# S7G7_footprint_simplified_w_ethernet_v1p.net
KiCad netlist of a schematic drawn in EAGLE
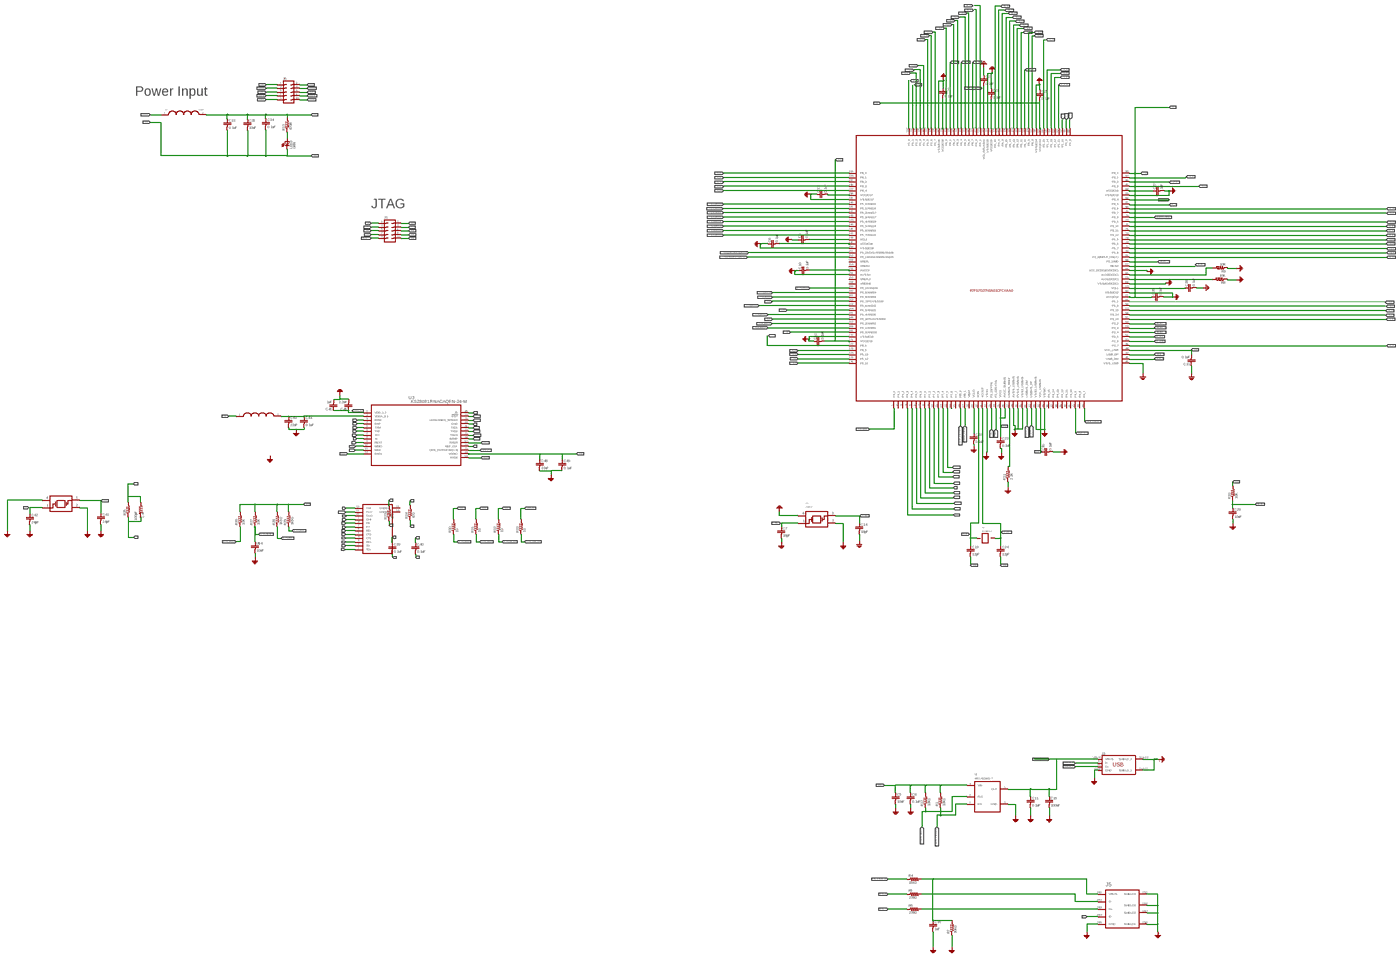
[diagram p0: schematic, sheet 1, overview]
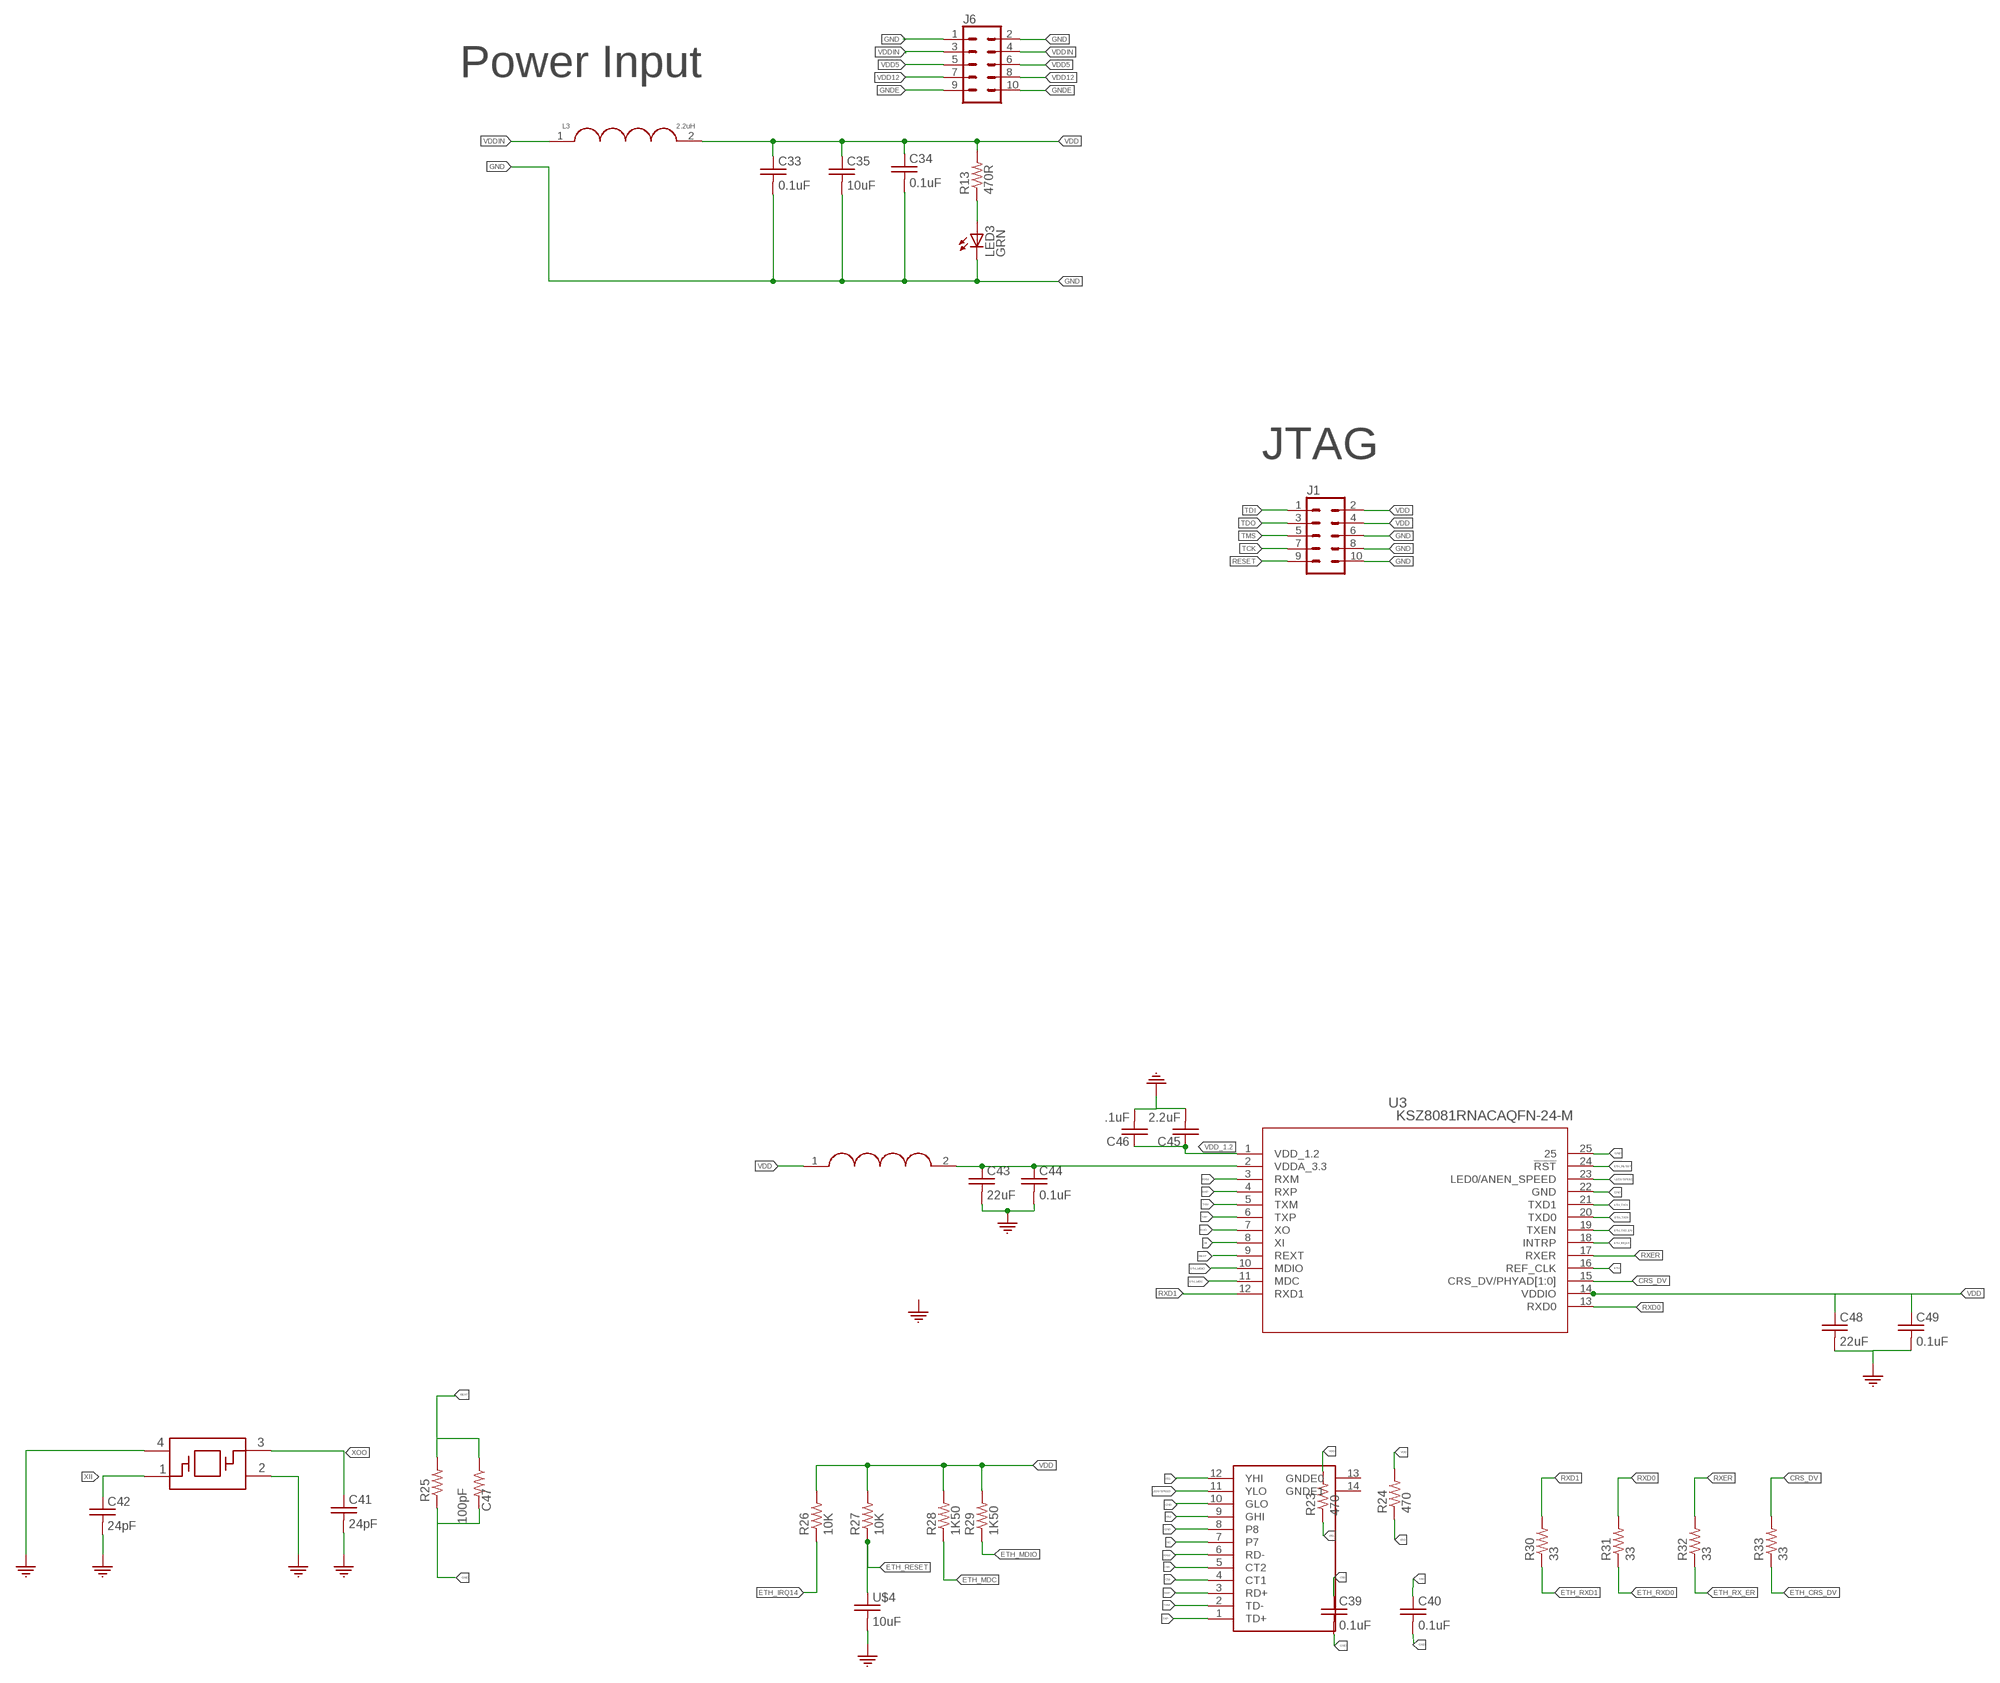
[diagram p1: schematic, sheet 1, part 1 of 4]
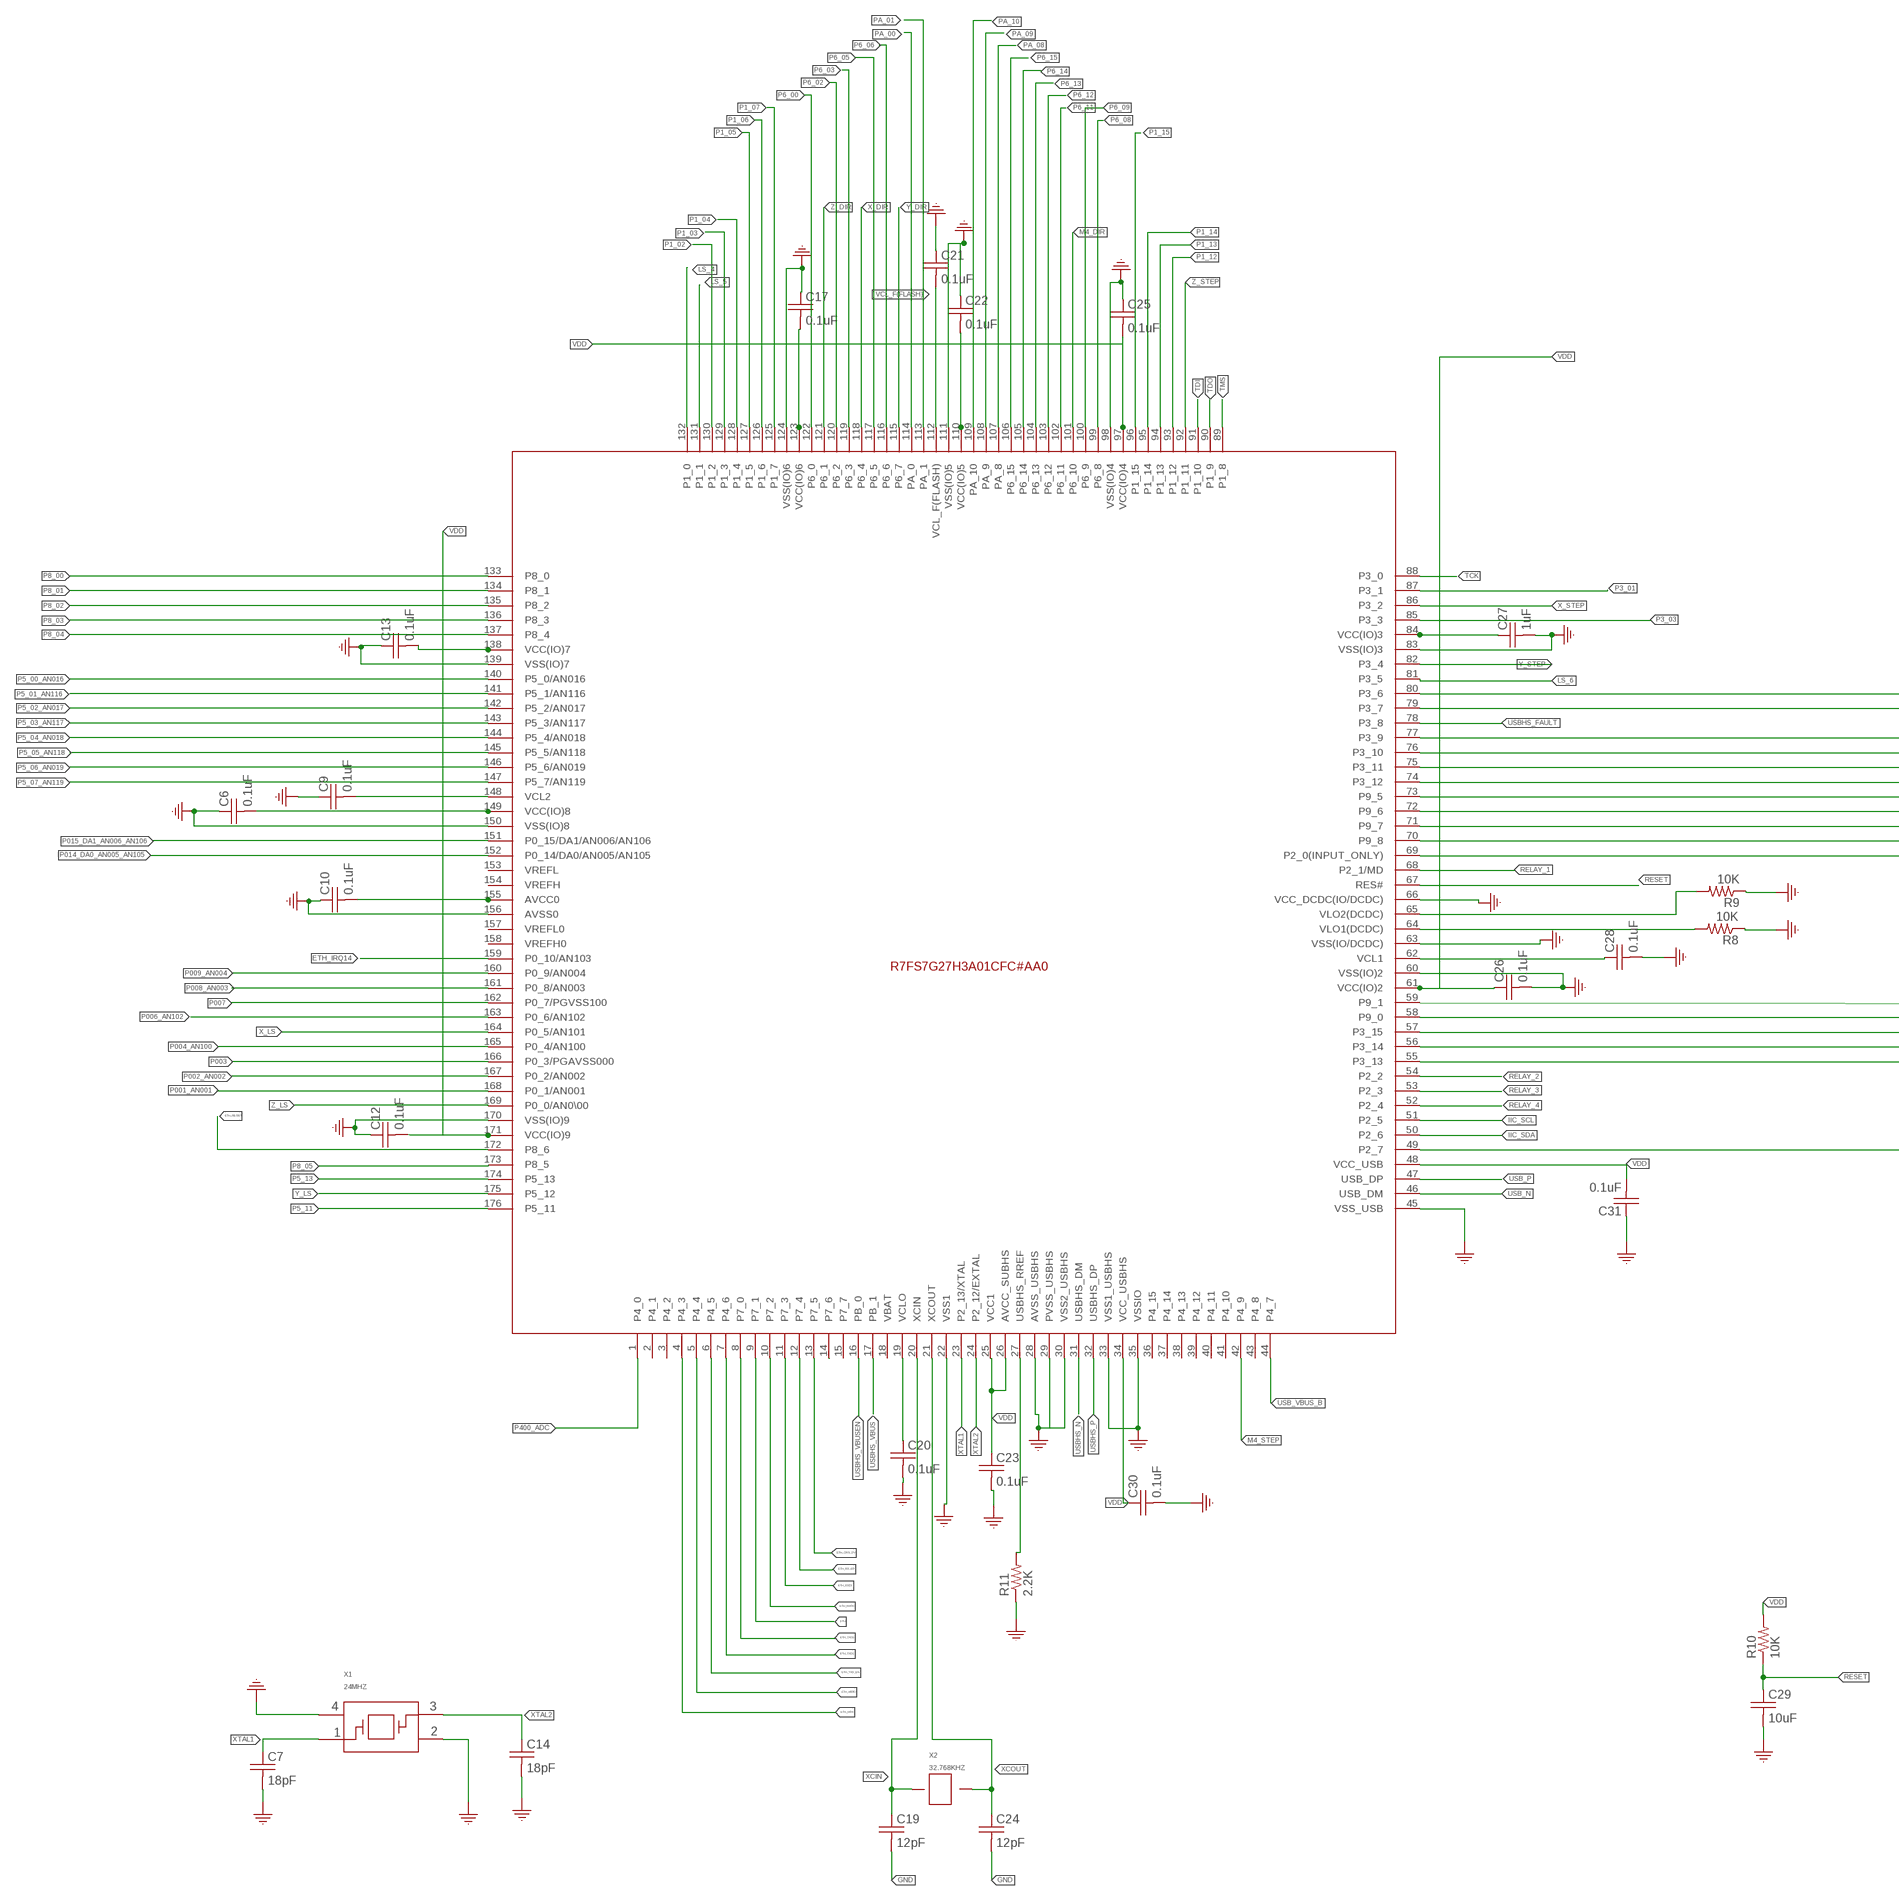
[diagram p2: schematic, sheet 1, part 2 of 4]
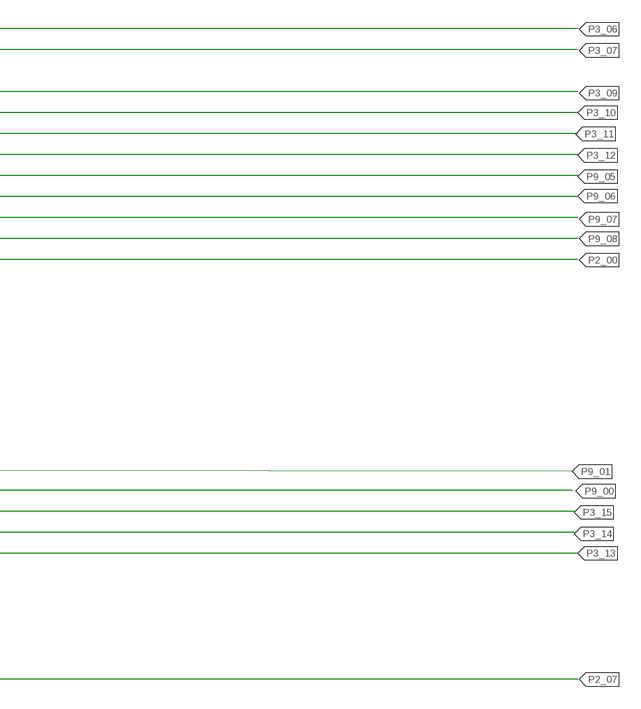
[diagram p3: schematic, sheet 1, part 3 of 4]
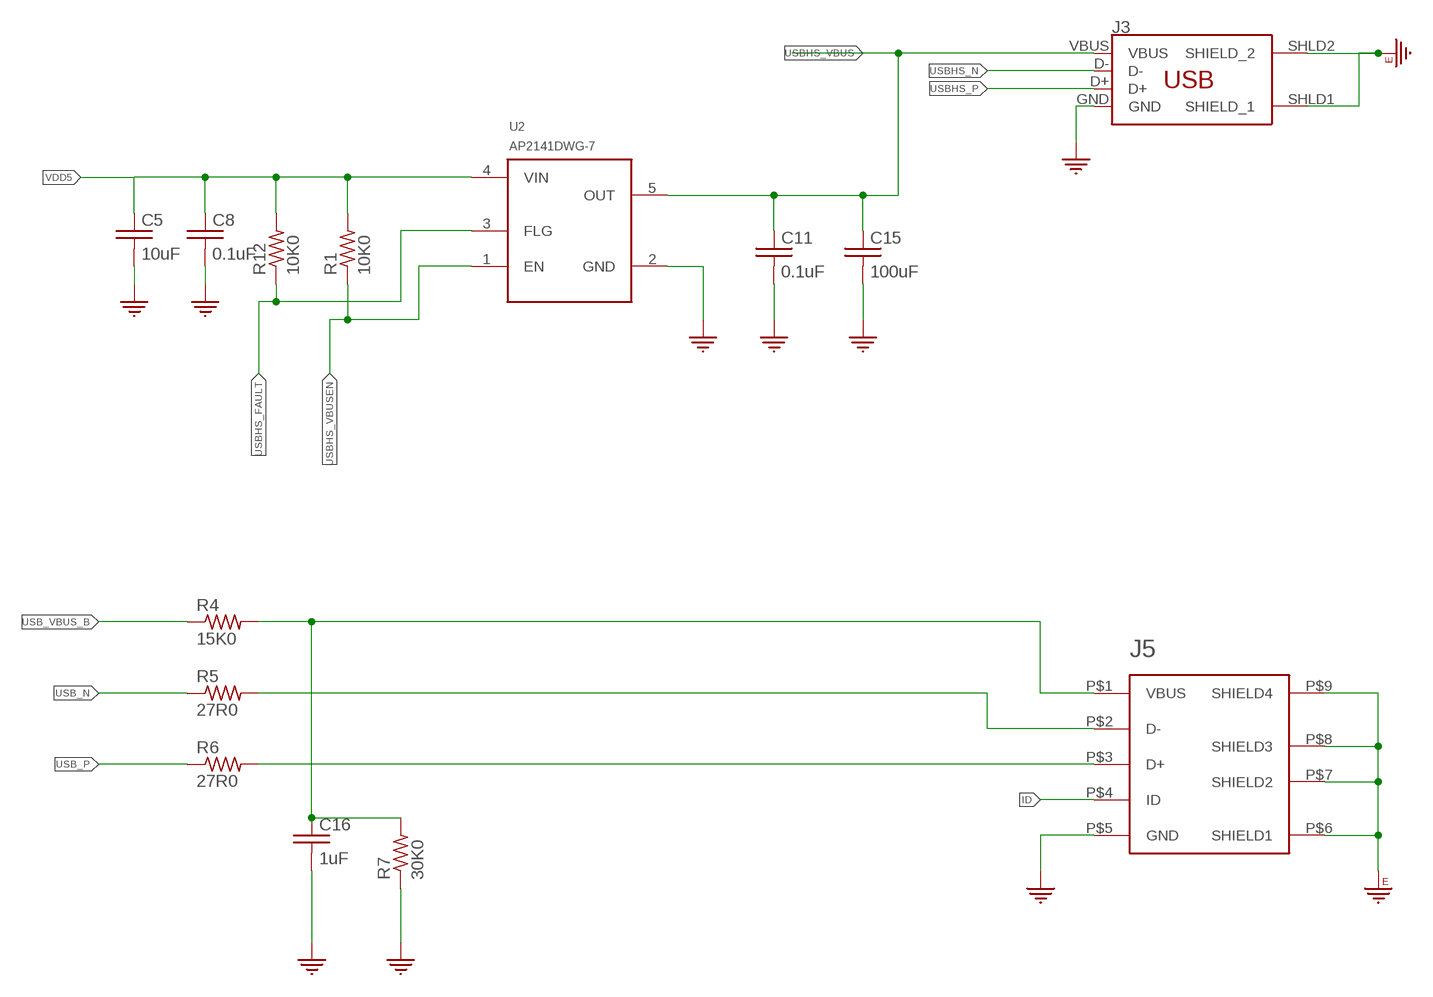
[diagram p4: schematic, sheet 1, part 4 of 4]

(export (version "E")
  (design (tool "Eeschema 10.0.6"))
  (components
    (comp (ref "C5")
      (value "10uF")
      (footprint "eagle-import:0402")
      (libsource (lib "eagle-import") (part "C_0402"))
    )
    (comp (ref "C6")
      (value "0.1uF")
      (footprint "eagle-import:0402")
      (libsource (lib "eagle-import") (part "C_0402"))
    )
    (comp (ref "C7")
      (value "18pF")
      (footprint "eagle-import:0402")
      (libsource (lib "eagle-import") (part "C_0402"))
    )
    (comp (ref "C8")
      (value "0.1uF")
      (footprint "eagle-import:0402")
      (libsource (lib "eagle-import") (part "C_0402"))
    )
    (comp (ref "C9")
      (value "0.1uF")
      (footprint "eagle-import:0402")
      (libsource (lib "eagle-import") (part "C_0402"))
    )
    (comp (ref "C10")
      (value "0.1uF")
      (footprint "eagle-import:0402")
      (libsource (lib "eagle-import") (part "C_0402"))
    )
    (comp (ref "C11")
      (value "0.1uF")
      (footprint "eagle-import:0402")
      (libsource (lib "eagle-import") (part "C_0402"))
    )
    (comp (ref "C12")
      (value "0.1uF")
      (footprint "eagle-import:0402")
      (libsource (lib "eagle-import") (part "C_0402"))
    )
    (comp (ref "C13")
      (value "0.1uF")
      (footprint "eagle-import:0402")
      (libsource (lib "eagle-import") (part "C_0402"))
    )
    (comp (ref "C14")
      (value "18pF")
      (footprint "eagle-import:0402")
      (libsource (lib "eagle-import") (part "C_0402"))
    )
    (comp (ref "C15")
      (value "100uF")
      (footprint "eagle-import:C1210")
      (libsource (lib "eagle-import") (part "C_1210"))
    )
    (comp (ref "C16")
      (value "1uF")
      (footprint "eagle-import:0402")
      (libsource (lib "eagle-import") (part "C_0402"))
    )
    (comp (ref "C17")
      (value "0.1uF")
      (footprint "eagle-import:0402")
      (libsource (lib "eagle-import") (part "C_0402"))
    )
    (comp (ref "C19")
      (value "12pF")
      (footprint "eagle-import:0402")
      (libsource (lib "eagle-import") (part "C_0402"))
    )
    (comp (ref "C20")
      (value "0.1uF")
      (footprint "eagle-import:0402")
      (libsource (lib "eagle-import") (part "C_0402"))
    )
    (comp (ref "C21")
      (value "0.1uF")
      (footprint "eagle-import:0402")
      (libsource (lib "eagle-import") (part "C_0402"))
    )
    (comp (ref "C22")
      (value "0.1uF")
      (footprint "eagle-import:0402")
      (libsource (lib "eagle-import") (part "C_0402"))
    )
    (comp (ref "C23")
      (value "0.1uF")
      (footprint "eagle-import:0402")
      (libsource (lib "eagle-import") (part "C_0402"))
    )
    (comp (ref "C24")
      (value "12pF")
      (footprint "eagle-import:0402")
      (libsource (lib "eagle-import") (part "C_0402"))
    )
    (comp (ref "C25")
      (value "0.1uF")
      (footprint "eagle-import:0402")
      (libsource (lib "eagle-import") (part "C_0402"))
    )
    (comp (ref "C26")
      (value "0.1uF")
      (footprint "eagle-import:0402")
      (libsource (lib "eagle-import") (part "C_0402"))
    )
    (comp (ref "C27")
      (value "1uF")
      (footprint "eagle-import:0402")
      (libsource (lib "eagle-import") (part "C_0402"))
    )
    (comp (ref "C28")
      (value "0.1uF")
      (footprint "eagle-import:0402")
      (libsource (lib "eagle-import") (part "C_0402"))
    )
    (comp (ref "C29")
      (value "10uF")
      (footprint "eagle-import:0402")
      (libsource (lib "eagle-import") (part "C_0402"))
    )
    (comp (ref "C30")
      (value "0.1uF")
      (footprint "eagle-import:0402")
      (libsource (lib "eagle-import") (part "C_0402"))
    )
    (comp (ref "C31")
      (value "0.1uF")
      (footprint "eagle-import:0402")
      (libsource (lib "eagle-import") (part "C_0402"))
    )
    (comp (ref "C33")
      (value "0.1uF")
      (footprint "eagle-import:0402")
      (libsource (lib "eagle-import") (part "C_0402"))
    )
    (comp (ref "C34")
      (value "0.1uF")
      (footprint "eagle-import:0402")
      (libsource (lib "eagle-import") (part "C_0402"))
    )
    (comp (ref "C35")
      (value "10uF")
      (footprint "eagle-import:0402")
      (libsource (lib "eagle-import") (part "C_0402"))
    )
    (comp (ref "C39")
      (value "0.1uF")
      (footprint "eagle-import:0402")
      (libsource (lib "eagle-import") (part "C_0402"))
    )
    (comp (ref "C40")
      (value "0.1uF")
      (footprint "eagle-import:0402")
      (libsource (lib "eagle-import") (part "C_0402"))
    )
    (comp (ref "C41")
      (value "24pF")
      (footprint "eagle-import:0402")
      (libsource (lib "eagle-import") (part "C_0402"))
    )
    (comp (ref "C42")
      (value "24pF")
      (footprint "eagle-import:0402")
      (libsource (lib "eagle-import") (part "C_0402"))
    )
    (comp (ref "C43")
      (value "22uF")
      (footprint "eagle-import:0603")
      (libsource (lib "eagle-import") (part "C_0603"))
    )
    (comp (ref "C44")
      (value "0.1uF")
      (footprint "eagle-import:0402")
      (libsource (lib "eagle-import") (part "C_0402"))
    )
    (comp (ref "C45")
      (value "2.2uF")
      (footprint "eagle-import:0402")
      (libsource (lib "eagle-import") (part "C_0402"))
    )
    (comp (ref "C46")
      (value ".1uF")
      (footprint "eagle-import:0402")
      (libsource (lib "eagle-import") (part "C_0402"))
    )
    (comp (ref "C47")
      (value "100pF")
      (footprint "eagle-import:0402")
      (libsource (lib "eagle-import") (part "R_0402"))
    )
    (comp (ref "C48")
      (value "22uF")
      (footprint "eagle-import:0603")
      (libsource (lib "eagle-import") (part "C_0603"))
    )
    (comp (ref "C49")
      (value "0.1uF")
      (footprint "eagle-import:0402")
      (libsource (lib "eagle-import") (part "C_0402"))
    )
    (comp (ref "FB2/2")
      (value "FB_0805_120_OHM")
      (footprint "eagle-import:0805")
      (libsource (lib "eagle-import") (part "FB_0805_120_OHM"))
    )
    (comp (ref "J1")
      (value "CONN_05X2PTH")
      (footprint "eagle-import:2X5")
      (libsource (lib "eagle-import") (part "CONN_05X2PTH"))
    )
    (comp (ref "J3")
      (value "USB_A")
      (footprint "eagle-import:USB_A_SMT")
      (libsource (lib "eagle-import") (part "USB_A"))
    )
    (comp (ref "J5")
      (value "USB_MICRO-B")
      (footprint "eagle-import:USB_MICRO-B")
      (libsource (lib "eagle-import") (part "USB_MICRO-B"))
    )
    (comp (ref "J6")
      (value "CONN_05X2PTH")
      (footprint "eagle-import:2X5")
      (libsource (lib "eagle-import") (part "CONN_05X2PTH"))
    )
    (comp (ref "L3")
      (value "2.2uH")
      (footprint "eagle-import:1008_(2520_METRIC)")
      (libsource (lib "eagle-import") (part "INDUCTOR_1008_2.2_MH_1.3A"))
    )
    (comp (ref "LED3")
      (value "LED_0805_GREEN")
      (footprint "eagle-import:LED_0805_GREEN")
      (libsource (lib "eagle-import") (part "LED_0805_GREEN"))
    )
    (comp (ref "R1")
      (value "10K0")
      (footprint "eagle-import:0402")
      (libsource (lib "eagle-import") (part "R_0402"))
    )
    (comp (ref "R4")
      (value "15K0")
      (footprint "eagle-import:0402")
      (libsource (lib "eagle-import") (part "R_0402"))
    )
    (comp (ref "R5")
      (value "27R0")
      (footprint "eagle-import:0402")
      (libsource (lib "eagle-import") (part "R_0402"))
    )
    (comp (ref "R6")
      (value "27R0")
      (footprint "eagle-import:0402")
      (libsource (lib "eagle-import") (part "R_0402"))
    )
    (comp (ref "R7")
      (value "30K0")
      (footprint "eagle-import:0402")
      (libsource (lib "eagle-import") (part "R_0402"))
    )
    (comp (ref "R8")
      (value "10K")
      (footprint "eagle-import:0402")
      (libsource (lib "eagle-import") (part "R_0402"))
    )
    (comp (ref "R9")
      (value "10K")
      (footprint "eagle-import:0402")
      (libsource (lib "eagle-import") (part "R_0402"))
    )
    (comp (ref "R10")
      (value "10K")
      (footprint "eagle-import:0402")
      (libsource (lib "eagle-import") (part "R_0402"))
    )
    (comp (ref "R11")
      (value "2.2K")
      (footprint "eagle-import:0402")
      (libsource (lib "eagle-import") (part "R_0402"))
    )
    (comp (ref "R12")
      (value "10K0")
      (footprint "eagle-import:0402")
      (libsource (lib "eagle-import") (part "R_0402"))
    )
    (comp (ref "R13")
      (value "470R")
      (footprint "eagle-import:0402")
      (libsource (lib "eagle-import") (part "R_0402"))
    )
    (comp (ref "R23")
      (value "470")
      (footprint "eagle-import:0402")
      (libsource (lib "eagle-import") (part "R_0402"))
    )
    (comp (ref "R24")
      (value "470")
      (footprint "eagle-import:0402")
      (libsource (lib "eagle-import") (part "R_0402"))
    )
    (comp (ref "R25")
      (value "6k49")
      (footprint "eagle-import:0402")
      (libsource (lib "eagle-import") (part "R_0402"))
    )
    (comp (ref "R26")
      (value "10K")
      (footprint "eagle-import:0402")
      (libsource (lib "eagle-import") (part "R_0402"))
    )
    (comp (ref "R27")
      (value "10K")
      (footprint "eagle-import:0402")
      (libsource (lib "eagle-import") (part "R_0402"))
    )
    (comp (ref "R28")
      (value "1K50")
      (footprint "eagle-import:0402")
      (libsource (lib "eagle-import") (part "R_0402"))
    )
    (comp (ref "R29")
      (value "1K50")
      (footprint "eagle-import:0402")
      (libsource (lib "eagle-import") (part "R_0402"))
    )
    (comp (ref "R30")
      (value "33")
      (footprint "eagle-import:0402")
      (libsource (lib "eagle-import") (part "R_0402"))
    )
    (comp (ref "R31")
      (value "33")
      (footprint "eagle-import:0402")
      (libsource (lib "eagle-import") (part "R_0402"))
    )
    (comp (ref "R32")
      (value "33")
      (footprint "eagle-import:0402")
      (libsource (lib "eagle-import") (part "R_0402"))
    )
    (comp (ref "R33")
      (value "33")
      (footprint "eagle-import:0402")
      (libsource (lib "eagle-import") (part "R_0402"))
    )
    (comp (ref "U$2")
      (value "RJ45_WITH_ELEC")
      (footprint "eagle-import:RJ45_TH_ELEC")
      (libsource (lib "eagle-import") (part "RJ45_WITH_ELEC"))
    )
    (comp (ref "U$3")
      (value "XTAL_25_MHZ")
      (footprint "eagle-import:SMD_3225")
      (libsource (lib "eagle-import") (part "XTAL_25_MHZ"))
    )
    (comp (ref "U$4")
      (value "10uF")
      (footprint "eagle-import:0402")
      (libsource (lib "eagle-import") (part "C_0402"))
    )
    (comp (ref "U2")
      (value "AP2141DWG-5")
      (footprint "eagle-import:SOT-23-5")
      (libsource (lib "eagle-import") (part "AP2141DWG-5"))
    )
    (comp (ref "U3")
      (value "KSZ8081RNACAQFN-24-M")
      (footprint "eagle-import:QFN-24-M")
      (fields (field (name "MANUFACTURER_PART_NUMBER") "KSZ8081RNACA"))
      (libsource (lib "eagle-import") (part "KSZ8081RNACAQFN-24-M"))
    )
    (comp (ref "U5")
      (value "S7G2_X_176")
      (footprint "eagle-import:LQFP176_24X24")
      (libsource (lib "eagle-import") (part "S7G2_X_176"))
    )
    (comp (ref "X1")
      (value "24MHZ")
      (footprint "eagle-import:SMD_3225")
      (libsource (lib "eagle-import") (part "XTAL_24_MHZ"))
    )
    (comp (ref "X2")
      (value "32.768KHZ")
      (footprint "eagle-import:SMD_X_2_PADS")
      (libsource (lib "eagle-import") (part "XTAL_32.768KHZ"))
    )
  )
  (nets
    (net (code "1") (name "C58") (class "Default")
      (node (ref "C39") (pin "P$1") (pinfunction "1_P$1") (pintype "passive"))
      (node (ref "U$2") (pin "4") (pinfunction "CT1_4") (pintype "bidirectional"))
    )
    (net (code "2") (name "C60") (class "Default")
      (node (ref "C40") (pin "P$1") (pinfunction "1_P$1") (pintype "passive"))
      (node (ref "U$2") (pin "5") (pinfunction "CT2_5") (pintype "bidirectional"))
    )
    (net (code "3") (name "CRS_DV") (class "Default")
      (node (ref "R33") (pin "P$2") (pinfunction "2_P$2") (pintype "passive"))
      (node (ref "U3") (pin "15") (pinfunction "CRS_DV/PHYAD[1:0]_15") (pintype "bidirectional"))
    )
    (net (code "4") (name "ETH") (class "Default")
      (node (ref "U3") (pin "16") (pinfunction "REF_CLK_16") (pintype "bidirectional"))
      (node (ref "U5") (pin "9") (pinfunction "P7_1_9") (pintype "bidirectional"))
    )
    (net (code "5") (name "ETH_CRS_DV") (class "Default")
      (node (ref "R33") (pin "P$1") (pinfunction "1_P$1") (pintype "passive"))
      (node (ref "U5") (pin "13") (pinfunction "P7_5_13") (pintype "bidirectional"))
    )
    (net (code "6") (name "ETH_IRQ14") (class "Default")
      (node (ref "R26") (pin "P$1") (pinfunction "1_P$1") (pintype "passive"))
      (node (ref "U3") (pin "18") (pinfunction "INTRP_18") (pintype "bidirectional"))
      (node (ref "U5") (pin "159") (pinfunction "P0_10/AN103_159") (pintype "bidirectional"))
    )
    (net (code "7") (name "ETH_MDC") (class "Default")
      (node (ref "R28") (pin "P$1") (pinfunction "1_P$1") (pintype "passive"))
      (node (ref "U3") (pin "11") (pinfunction "MDC_11") (pintype "input"))
      (node (ref "U5") (pin "4") (pinfunction "P4_3_4") (pintype "bidirectional"))
    )
    (net (code "8") (name "ETH_MDIO") (class "Default")
      (node (ref "R29") (pin "P$1") (pinfunction "1_P$1") (pintype "passive"))
      (node (ref "U3") (pin "10") (pinfunction "MDIO_10") (pintype "bidirectional"))
      (node (ref "U5") (pin "5") (pinfunction "P4_4_5") (pintype "bidirectional"))
    )
    (net (code "9") (name "ETH_RESET") (class "Default")
      (node (ref "R27") (pin "P$1") (pinfunction "1_P$1") (pintype "passive"))
      (node (ref "U$4") (pin "P$1") (pinfunction "1_P$1") (pintype "passive"))
      (node (ref "U3") (pin "24") (pinfunction "~{RST}_24") (pintype "input"))
      (node (ref "U5") (pin "172") (pinfunction "P8_6_172") (pintype "bidirectional"))
    )
    (net (code "10") (name "ETH_RXD0") (class "Default")
      (node (ref "R31") (pin "P$1") (pinfunction "1_P$1") (pintype "passive"))
      (node (ref "U5") (pin "10") (pinfunction "P7_2_10") (pintype "bidirectional"))
    )
    (net (code "11") (name "ETH_RXD1") (class "Default")
      (node (ref "R30") (pin "P$1") (pinfunction "1_P$1") (pintype "passive"))
      (node (ref "U5") (pin "11") (pinfunction "P7_3_11") (pintype "bidirectional"))
    )
    (net (code "12") (name "ETH_RX_ER") (class "Default")
      (node (ref "R32") (pin "P$1") (pinfunction "1_P$1") (pintype "passive"))
      (node (ref "U5") (pin "12") (pinfunction "P7_4_12") (pintype "bidirectional"))
    )
    (net (code "13") (name "ETH_TXD0") (class "Default")
      (node (ref "U3") (pin "20") (pinfunction "TXD0_20") (pintype "input"))
      (node (ref "U5") (pin "8") (pinfunction "P7_0_8") (pintype "bidirectional"))
    )
    (net (code "14") (name "ETH_TXD1") (class "Default")
      (node (ref "U3") (pin "21") (pinfunction "TXD1_21") (pintype "bidirectional"))
      (node (ref "U5") (pin "7") (pinfunction "P4_6_7") (pintype "bidirectional"))
    )
    (net (code "15") (name "ETH_TXD_EN") (class "Default")
      (node (ref "U3") (pin "19") (pinfunction "TXEN_19") (pintype "input"))
      (node (ref "U5") (pin "6") (pinfunction "P4_5_6") (pintype "bidirectional"))
    )
    (net (code "16") (name "GND") (class "Default")
      (node (ref "C10") (pin "P$1") (pinfunction "1_P$1") (pintype "passive"))
      (node (ref "C11") (pin "P$2") (pinfunction "2_P$2") (pintype "passive"))
      (node (ref "C12") (pin "P$1") (pinfunction "1_P$1") (pintype "passive"))
      (node (ref "C13") (pin "P$1") (pinfunction "1_P$1") (pintype "passive"))
      (node (ref "C14") (pin "P$2") (pinfunction "2_P$2") (pintype "passive"))
      (node (ref "C15") (pin "2") (pinfunction "2_2") (pintype "passive"))
      (node (ref "C16") (pin "P$2") (pinfunction "2_P$2") (pintype "passive"))
      (node (ref "C17") (pin "P$1") (pinfunction "1_P$1") (pintype "passive"))
      (node (ref "C19") (pin "P$2") (pinfunction "2_P$2") (pintype "passive"))
      (node (ref "C20") (pin "P$2") (pinfunction "2_P$2") (pintype "passive"))
      (node (ref "C21") (pin "P$1") (pinfunction "1_P$1") (pintype "passive"))
      (node (ref "C22") (pin "P$1") (pinfunction "1_P$1") (pintype "passive"))
      (node (ref "C23") (pin "P$2") (pinfunction "2_P$2") (pintype "passive"))
      (node (ref "C24") (pin "P$2") (pinfunction "2_P$2") (pintype "passive"))
      (node (ref "C25") (pin "P$1") (pinfunction "1_P$1") (pintype "passive"))
      (node (ref "C26") (pin "P$2") (pinfunction "2_P$2") (pintype "passive"))
      (node (ref "C27") (pin "P$2") (pinfunction "2_P$2") (pintype "passive"))
      (node (ref "C28") (pin "P$2") (pinfunction "2_P$2") (pintype "passive"))
      (node (ref "C29") (pin "P$2") (pinfunction "2_P$2") (pintype "passive"))
      (node (ref "C30") (pin "P$2") (pinfunction "2_P$2") (pintype "passive"))
      (node (ref "C31") (pin "P$1") (pinfunction "1_P$1") (pintype "passive"))
      (node (ref "C33") (pin "P$2") (pinfunction "2_P$2") (pintype "passive"))
      (node (ref "C34") (pin "P$2") (pinfunction "2_P$2") (pintype "passive"))
      (node (ref "C35") (pin "P$2") (pinfunction "2_P$2") (pintype "passive"))
      (node (ref "C39") (pin "P$2") (pinfunction "2_P$2") (pintype "passive"))
      (node (ref "C40") (pin "P$2") (pinfunction "2_P$2") (pintype "passive"))
      (node (ref "C41") (pin "P$2") (pinfunction "2_P$2") (pintype "passive"))
      (node (ref "C42") (pin "P$2") (pinfunction "2_P$2") (pintype "passive"))
      (node (ref "C43") (pin "2") (pinfunction "2_2") (pintype "passive"))
      (node (ref "C44") (pin "P$2") (pinfunction "2_P$2") (pintype "passive"))
      (node (ref "C45") (pin "P$2") (pinfunction "2_P$2") (pintype "passive"))
      (node (ref "C46") (pin "P$2") (pinfunction "2_P$2") (pintype "passive"))
      (node (ref "C47") (pin "P$2") (pinfunction "2_P$2") (pintype "passive"))
      (node (ref "C48") (pin "2") (pinfunction "2_2") (pintype "passive"))
      (node (ref "C49") (pin "P$2") (pinfunction "2_P$2") (pintype "passive"))
      (node (ref "C5") (pin "P$2") (pinfunction "2_P$2") (pintype "passive"))
      (node (ref "C6") (pin "P$1") (pinfunction "1_P$1") (pintype "passive"))
      (node (ref "C7") (pin "P$2") (pinfunction "2_P$2") (pintype "passive"))
      (node (ref "C8") (pin "P$2") (pinfunction "2_P$2") (pintype "passive"))
      (node (ref "C9") (pin "P$1") (pinfunction "1_P$1") (pintype "passive"))
      (node (ref "J1") (pin "10") (pinfunction "10_10") (pintype "passive"))
      (node (ref "J1") (pin "6") (pinfunction "6_6") (pintype "passive"))
      (node (ref "J1") (pin "8") (pinfunction "8_8") (pintype "passive"))
      (node (ref "J3") (pin "GND") (pinfunction "GND_GND") (pintype "power_in"))
      (node (ref "J5") (pin "P$5") (pinfunction "GND_P$5") (pintype "bidirectional"))
      (node (ref "J6") (pin "1") (pinfunction "1_1") (pintype "passive"))
      (node (ref "J6") (pin "2") (pinfunction "2_2") (pintype "passive"))
      (node (ref "LED3") (pin "C") (pinfunction "C_C") (pintype "passive"))
      (node (ref "R11") (pin "P$1") (pinfunction "1_P$1") (pintype "passive"))
      (node (ref "R25") (pin "P$1") (pinfunction "1_P$1") (pintype "passive"))
      (node (ref "R7") (pin "P$1") (pinfunction "1_P$1") (pintype "passive"))
      (node (ref "R8") (pin "P$1") (pinfunction "1_P$1") (pintype "passive"))
      (node (ref "R9") (pin "P$1") (pinfunction "1_P$1") (pintype "passive"))
      (node (ref "U$2") (pin "10") (pinfunction "GLO_10") (pintype "bidirectional"))
      (node (ref "U$2") (pin "8") (pinfunction "P8_8") (pintype "bidirectional"))
      (node (ref "U$3") (pin "2") (pinfunction "2_2") (pintype "bidirectional"))
      (node (ref "U$3") (pin "4") (pinfunction "4_4") (pintype "bidirectional"))
      (node (ref "U$4") (pin "P$2") (pinfunction "2_P$2") (pintype "passive"))
      (node (ref "U2") (pin "2") (pinfunction "GND_2") (pintype "input"))
      (node (ref "U3") (pin "22") (pinfunction "GND_22") (pintype "power_in"))
      (node (ref "U3") (pin "25") (pinfunction "25_25") (pintype "passive"))
      (node (ref "U5") (pin "111") (pinfunction "VSS(IO)5_111") (pintype "bidirectional"))
      (node (ref "U5") (pin "124") (pinfunction "VSS(IO)6_124") (pintype "bidirectional"))
      (node (ref "U5") (pin "139") (pinfunction "VSS(IO)7_139") (pintype "bidirectional"))
      (node (ref "U5") (pin "150") (pinfunction "VSS(IO)8_150") (pintype "bidirectional"))
      (node (ref "U5") (pin "156") (pinfunction "AVSS0_156") (pintype "bidirectional"))
      (node (ref "U5") (pin "170") (pinfunction "VSS(IO)9_170") (pintype "bidirectional"))
      (node (ref "U5") (pin "22") (pinfunction "VSS1_22") (pintype "bidirectional"))
      (node (ref "U5") (pin "28") (pinfunction "AVSS_USBHS_28") (pintype "bidirectional"))
      (node (ref "U5") (pin "29") (pinfunction "PVSS_USBHS_29") (pintype "bidirectional"))
      (node (ref "U5") (pin "30") (pinfunction "VSS2_USBHS_30") (pintype "bidirectional"))
      (node (ref "U5") (pin "33") (pinfunction "VSS1_USBHS_33") (pintype "bidirectional"))
      (node (ref "U5") (pin "35") (pinfunction "VSSIO_35") (pintype "bidirectional"))
      (node (ref "U5") (pin "45") (pinfunction "VSS_USB_45") (pintype "bidirectional"))
      (node (ref "U5") (pin "60") (pinfunction "VSS(IO)2_60") (pintype "bidirectional"))
      (node (ref "U5") (pin "63") (pinfunction "VSS(IO/DCDC)_63") (pintype "bidirectional"))
      (node (ref "U5") (pin "66") (pinfunction "VCC_DCDC(IO/DCDC)_66") (pintype "bidirectional"))
      (node (ref "U5") (pin "83") (pinfunction "VSS(IO)3_83") (pintype "bidirectional"))
      (node (ref "U5") (pin "98") (pinfunction "VSS(IO)4_98") (pintype "bidirectional"))
      (node (ref "X1") (pin "2") (pinfunction "2_2") (pintype "bidirectional"))
      (node (ref "X1") (pin "4") (pinfunction "4_4") (pintype "bidirectional"))
    )
    (net (code "17") (name "GNDE") (class "Default")
      (node (ref "J3") (pin "SHLD1") (pinfunction "SHIELD_1_SHLD1") (pintype "bidirectional"))
      (node (ref "J3") (pin "SHLD2") (pinfunction "SHIELD_2_SHLD2") (pintype "bidirectional"))
      (node (ref "J5") (pin "P$6") (pinfunction "SHIELD1_P$6") (pintype "bidirectional"))
      (node (ref "J5") (pin "P$7") (pinfunction "SHIELD2_P$7") (pintype "bidirectional"))
      (node (ref "J5") (pin "P$8") (pinfunction "SHIELD3_P$8") (pintype "bidirectional"))
      (node (ref "J5") (pin "P$9") (pinfunction "SHIELD4_P$9") (pintype "bidirectional"))
      (node (ref "J6") (pin "10") (pinfunction "10_10") (pintype "passive"))
      (node (ref "J6") (pin "9") (pinfunction "9_9") (pintype "passive"))
    )
    (net (code "18") (name "ID") (class "Default")
      (node (ref "J5") (pin "P$4") (pinfunction "ID_P$4") (pintype "bidirectional"))
    )
    (net (code "19") (name "IIC_SCL") (class "Default")
      (node (ref "U5") (pin "51") (pinfunction "P2_5_51") (pintype "bidirectional"))
    )
    (net (code "20") (name "IIC_SDA") (class "Default")
      (node (ref "U5") (pin "50") (pinfunction "P2_6_50") (pintype "bidirectional"))
    )
    (net (code "21") (name "LED1{slash}SPEED") (class "Default")
      (node (ref "U$2") (pin "11") (pinfunction "YLO_11") (pintype "bidirectional"))
      (node (ref "U3") (pin "23") (pinfunction "LED0/ANEN_SPEED_23") (pintype "bidirectional"))
    )
    (net (code "22") (name "LS_4") (class "Default")
      (node (ref "U5") (pin "132") (pinfunction "P1_0_132") (pintype "bidirectional"))
    )
    (net (code "23") (name "LS_5") (class "Default")
      (node (ref "U5") (pin "131") (pinfunction "P1_1_131") (pintype "bidirectional"))
    )
    (net (code "24") (name "LS_6") (class "Default")
      (node (ref "U5") (pin "81") (pinfunction "P3_5_81") (pintype "bidirectional"))
    )
    (net (code "25") (name "M4_DIR") (class "Default")
      (node (ref "U5") (pin "101") (pinfunction "P6_10_101") (pintype "bidirectional"))
    )
    (net (code "26") (name "M4_STEP") (class "Default")
      (node (ref "U5") (pin "42") (pinfunction "P4_9_42") (pintype "bidirectional"))
    )
    (net (code "27") (name "NC") (class "Default")
      (node (ref "U$2") (pin "7") (pinfunction "P7_7") (pintype "bidirectional"))
    )
    (net (code "28") (name "Net-(C9-2)") (class "Default")
      (node (ref "C9") (pin "P$2") (pinfunction "2_P$2") (pintype "passive"))
      (node (ref "U5") (pin "148") (pinfunction "VCL2_148") (pintype "bidirectional"))
    )
    (net (code "29") (name "Net-(C16-1)") (class "Default")
      (node (ref "C16") (pin "P$1") (pinfunction "1_P$1") (pintype "passive"))
      (node (ref "J5") (pin "P$1") (pinfunction "VBUS_P$1") (pintype "bidirectional"))
      (node (ref "R4") (pin "P$2") (pinfunction "2_P$2") (pintype "passive"))
      (node (ref "R7") (pin "P$2") (pinfunction "2_P$2") (pintype "passive"))
    )
    (net (code "30") (name "Net-(C20-1)") (class "Default")
      (node (ref "C20") (pin "P$1") (pinfunction "1_P$1") (pintype "passive"))
      (node (ref "U5") (pin "19") (pinfunction "VCLO_19") (pintype "bidirectional"))
    )
    (net (code "31") (name "Net-(C28-1)") (class "Default")
      (node (ref "C28") (pin "P$1") (pinfunction "1_P$1") (pintype "passive"))
      (node (ref "U5") (pin "62") (pinfunction "VCL1_62") (pintype "bidirectional"))
    )
    (net (code "32") (name "Net-(C44-1)") (class "Default")
      (node (ref "C43") (pin "1") (pinfunction "1_1") (pintype "passive"))
      (node (ref "C44") (pin "P$1") (pinfunction "1_P$1") (pintype "passive"))
      (node (ref "FB2/2") (pin "2") (pinfunction "P$2_2") (pintype "bidirectional"))
      (node (ref "U3") (pin "2") (pinfunction "VDDA_3.3_2") (pintype "power_in"))
    )
    (net (code "33") (name "Net-(J5-D+)") (class "Default")
      (node (ref "J5") (pin "P$3") (pinfunction "D+_P$3") (pintype "bidirectional"))
      (node (ref "R6") (pin "P$2") (pinfunction "2_P$2") (pintype "passive"))
    )
    (net (code "34") (name "Net-(J5-D-)") (class "Default")
      (node (ref "J5") (pin "P$2") (pinfunction "D-_P$2") (pintype "bidirectional"))
      (node (ref "R5") (pin "P$2") (pinfunction "2_P$2") (pintype "passive"))
    )
    (net (code "35") (name "Net-(R8-2)") (class "Default")
      (node (ref "R8") (pin "P$2") (pinfunction "2_P$2") (pintype "passive"))
      (node (ref "U5") (pin "64") (pinfunction "VLO1(DCDC)_64") (pintype "bidirectional"))
    )
    (net (code "36") (name "Net-(R9-2)") (class "Default")
      (node (ref "R9") (pin "P$2") (pinfunction "2_P$2") (pintype "passive"))
      (node (ref "U5") (pin "65") (pinfunction "VLO2(DCDC)_65") (pintype "bidirectional"))
    )
    (net (code "37") (name "Net-(R11-2)") (class "Default")
      (node (ref "R11") (pin "P$2") (pinfunction "2_P$2") (pintype "passive"))
      (node (ref "U5") (pin "27") (pinfunction "USBHS_RREF_27") (pintype "bidirectional"))
    )
    (net (code "38") (name "Net-(R13-1)") (class "Default")
      (node (ref "LED3") (pin "A") (pinfunction "A_A") (pintype "passive"))
      (node (ref "R13") (pin "P$1") (pinfunction "1_P$1") (pintype "passive"))
    )
    (net (code "39") (name "P1_02") (class "Default")
      (node (ref "U5") (pin "130") (pinfunction "P1_2_130") (pintype "bidirectional"))
    )
    (net (code "40") (name "P1_03") (class "Default")
      (node (ref "U5") (pin "129") (pinfunction "P1_3_129") (pintype "bidirectional"))
    )
    (net (code "41") (name "P1_04") (class "Default")
      (node (ref "U5") (pin "128") (pinfunction "P1_4_128") (pintype "bidirectional"))
    )
    (net (code "42") (name "P1_05") (class "Default")
      (node (ref "U5") (pin "127") (pinfunction "P1_5_127") (pintype "bidirectional"))
    )
    (net (code "43") (name "P1_06") (class "Default")
      (node (ref "U5") (pin "126") (pinfunction "P1_6_126") (pintype "bidirectional"))
    )
    (net (code "44") (name "P1_07") (class "Default")
      (node (ref "U5") (pin "125") (pinfunction "P1_7_125") (pintype "bidirectional"))
    )
    (net (code "45") (name "P1_12") (class "Default")
      (node (ref "U5") (pin "93") (pinfunction "P1_12_93") (pintype "bidirectional"))
    )
    (net (code "46") (name "P1_13") (class "Default")
      (node (ref "U5") (pin "94") (pinfunction "P1_13_94") (pintype "bidirectional"))
    )
    (net (code "47") (name "P1_14") (class "Default")
      (node (ref "U5") (pin "95") (pinfunction "P1_14_95") (pintype "bidirectional"))
    )
    (net (code "48") (name "P1_15") (class "Default")
      (node (ref "U5") (pin "96") (pinfunction "P1_15_96") (pintype "bidirectional"))
    )
    (net (code "49") (name "P001_AN001") (class "Default")
      (node (ref "U5") (pin "168") (pinfunction "P0_1/AN001_168") (pintype "bidirectional"))
    )
    (net (code "50") (name "P2_00") (class "Default")
      (node (ref "U5") (pin "69") (pinfunction "P2_0(INPUT_ONLY)_69") (pintype "bidirectional"))
    )
    (net (code "51") (name "P2_07") (class "Default")
      (node (ref "U5") (pin "49") (pinfunction "P2_7_49") (pintype "bidirectional"))
    )
    (net (code "52") (name "P002_AN002") (class "Default")
      (node (ref "U5") (pin "167") (pinfunction "P0_2/AN002_167") (pintype "bidirectional"))
    )
    (net (code "53") (name "P003") (class "Default")
      (node (ref "U5") (pin "166") (pinfunction "P0_3/PGAVSS000_166") (pintype "bidirectional"))
    )
    (net (code "54") (name "P3_01") (class "Default")
      (node (ref "U5") (pin "87") (pinfunction "P3_1_87") (pintype "bidirectional"))
    )
    (net (code "55") (name "P3_03") (class "Default")
      (node (ref "U5") (pin "85") (pinfunction "P3_3_85") (pintype "bidirectional"))
    )
    (net (code "56") (name "P3_06") (class "Default")
      (node (ref "U5") (pin "80") (pinfunction "P3_6_80") (pintype "bidirectional"))
    )
    (net (code "57") (name "P3_07") (class "Default")
      (node (ref "U5") (pin "79") (pinfunction "P3_7_79") (pintype "bidirectional"))
    )
    (net (code "58") (name "P3_09") (class "Default")
      (node (ref "U5") (pin "77") (pinfunction "P3_9_77") (pintype "bidirectional"))
    )
    (net (code "59") (name "P3_10") (class "Default")
      (node (ref "U5") (pin "76") (pinfunction "P3_10_76") (pintype "bidirectional"))
    )
    (net (code "60") (name "P3_11") (class "Default")
      (node (ref "U5") (pin "75") (pinfunction "P3_11_75") (pintype "bidirectional"))
    )
    (net (code "61") (name "P3_12") (class "Default")
      (node (ref "U5") (pin "74") (pinfunction "P3_12_74") (pintype "bidirectional"))
    )
    (net (code "62") (name "P3_13") (class "Default")
      (node (ref "U5") (pin "55") (pinfunction "P3_13_55") (pintype "bidirectional"))
    )
    (net (code "63") (name "P3_14") (class "Default")
      (node (ref "U5") (pin "56") (pinfunction "P3_14_56") (pintype "bidirectional"))
    )
    (net (code "64") (name "P3_15") (class "Default")
      (node (ref "U5") (pin "57") (pinfunction "P3_15_57") (pintype "bidirectional"))
    )
    (net (code "65") (name "P004_AN100") (class "Default")
      (node (ref "U5") (pin "165") (pinfunction "P0_4/AN100_165") (pintype "bidirectional"))
    )
    (net (code "66") (name "P5_00_AN016") (class "Default")
      (node (ref "U5") (pin "140") (pinfunction "P5_0/AN016_140") (pintype "bidirectional"))
    )
    (net (code "67") (name "P5_01_AN116") (class "Default")
      (node (ref "U5") (pin "141") (pinfunction "P5_1/AN116_141") (pintype "bidirectional"))
    )
    (net (code "68") (name "P5_02_AN017") (class "Default")
      (node (ref "U5") (pin "142") (pinfunction "P5_2/AN017_142") (pintype "bidirectional"))
    )
    (net (code "69") (name "P5_03_AN117") (class "Default")
      (node (ref "U5") (pin "143") (pinfunction "P5_3/AN117_143") (pintype "bidirectional"))
    )
    (net (code "70") (name "P5_04_AN018") (class "Default")
      (node (ref "U5") (pin "144") (pinfunction "P5_4/AN018_144") (pintype "bidirectional"))
    )
    (net (code "71") (name "P5_05_AN118") (class "Default")
      (node (ref "U5") (pin "145") (pinfunction "P5_5/AN118_145") (pintype "bidirectional"))
    )
    (net (code "72") (name "P5_06_AN019") (class "Default")
      (node (ref "U5") (pin "146") (pinfunction "P5_6/AN019_146") (pintype "bidirectional"))
    )
    (net (code "73") (name "P5_07_AN119") (class "Default")
      (node (ref "U5") (pin "147") (pinfunction "P5_7/AN119_147") (pintype "bidirectional"))
    )
    (net (code "74") (name "P5_11") (class "Default")
      (node (ref "U5") (pin "176") (pinfunction "P5_11_176") (pintype "bidirectional"))
    )
    (net (code "75") (name "P5_13") (class "Default")
      (node (ref "U5") (pin "174") (pinfunction "P5_13_174") (pintype "bidirectional"))
    )
    (net (code "76") (name "P6_00") (class "Default")
      (node (ref "U5") (pin "122") (pinfunction "P6_0_122") (pintype "bidirectional"))
    )
    (net (code "77") (name "P6_02") (class "Default")
      (node (ref "U5") (pin "120") (pinfunction "P6_2_120") (pintype "bidirectional"))
    )
    (net (code "78") (name "P6_03") (class "Default")
      (node (ref "U5") (pin "119") (pinfunction "P6_3_119") (pintype "bidirectional"))
    )
    (net (code "79") (name "P6_05") (class "Default")
      (node (ref "U5") (pin "117") (pinfunction "P6_5_117") (pintype "bidirectional"))
    )
    (net (code "80") (name "P6_06") (class "Default")
      (node (ref "U5") (pin "116") (pinfunction "P6_6_116") (pintype "bidirectional"))
    )
    (net (code "81") (name "P6_08") (class "Default")
      (node (ref "U5") (pin "99") (pinfunction "P6_8_99") (pintype "bidirectional"))
    )
    (net (code "82") (name "P6_09") (class "Default")
      (node (ref "U5") (pin "100") (pinfunction "P6_9_100") (pintype "bidirectional"))
    )
    (net (code "83") (name "P6_11") (class "Default")
      (node (ref "U5") (pin "102") (pinfunction "P6_11_102") (pintype "bidirectional"))
    )
    (net (code "84") (name "P6_12") (class "Default")
      (node (ref "U5") (pin "103") (pinfunction "P6_12_103") (pintype "bidirectional"))
    )
    (net (code "85") (name "P6_13") (class "Default")
      (node (ref "U5") (pin "104") (pinfunction "P6_13_104") (pintype "bidirectional"))
    )
    (net (code "86") (name "P6_14") (class "Default")
      (node (ref "U5") (pin "105") (pinfunction "P6_14_105") (pintype "bidirectional"))
    )
    (net (code "87") (name "P6_15") (class "Default")
      (node (ref "U5") (pin "106") (pinfunction "P6_15_106") (pintype "bidirectional"))
    )
    (net (code "88") (name "P006_AN102") (class "Default")
      (node (ref "U5") (pin "163") (pinfunction "P0_6/AN102_163") (pintype "bidirectional"))
    )
    (net (code "89") (name "P007") (class "Default")
      (node (ref "U5") (pin "162") (pinfunction "P0_7/PGVSS100_162") (pintype "bidirectional"))
    )
    (net (code "90") (name "P8_00") (class "Default")
      (node (ref "U5") (pin "133") (pinfunction "P8_0_133") (pintype "bidirectional"))
    )
    (net (code "91") (name "P8_01") (class "Default")
      (node (ref "U5") (pin "134") (pinfunction "P8_1_134") (pintype "bidirectional"))
    )
    (net (code "92") (name "P8_02") (class "Default")
      (node (ref "U5") (pin "135") (pinfunction "P8_2_135") (pintype "bidirectional"))
    )
    (net (code "93") (name "P8_03") (class "Default")
      (node (ref "U5") (pin "136") (pinfunction "P8_3_136") (pintype "bidirectional"))
    )
    (net (code "94") (name "P8_04") (class "Default")
      (node (ref "U5") (pin "137") (pinfunction "P8_4_137") (pintype "bidirectional"))
    )
    (net (code "95") (name "P8_05") (class "Default")
      (node (ref "U5") (pin "173") (pinfunction "P8_5_173") (pintype "bidirectional"))
    )
    (net (code "96") (name "P008_AN003") (class "Default")
      (node (ref "U5") (pin "161") (pinfunction "P0_8/AN003_161") (pintype "bidirectional"))
    )
    (net (code "97") (name "P9_00") (class "Default")
      (node (ref "U5") (pin "58") (pinfunction "P9_0_58") (pintype "bidirectional"))
    )
    (net (code "98") (name "P9_01") (class "Default")
      (node (ref "U5") (pin "59") (pinfunction "P9_1_59") (pintype "bidirectional"))
    )
    (net (code "99") (name "P9_05") (class "Default")
      (node (ref "U5") (pin "73") (pinfunction "P9_5_73") (pintype "bidirectional"))
    )
    (net (code "100") (name "P9_06") (class "Default")
      (node (ref "U5") (pin "72") (pinfunction "P9_6_72") (pintype "bidirectional"))
    )
    (net (code "101") (name "P9_07") (class "Default")
      (node (ref "U5") (pin "71") (pinfunction "P9_7_71") (pintype "bidirectional"))
    )
    (net (code "102") (name "P9_08") (class "Default")
      (node (ref "U5") (pin "70") (pinfunction "P9_8_70") (pintype "bidirectional"))
    )
    (net (code "103") (name "P009_AN004") (class "Default")
      (node (ref "U5") (pin "160") (pinfunction "P0_9/AN004_160") (pintype "bidirectional"))
    )
    (net (code "104") (name "P014_DA0_AN005_AN105") (class "Default")
      (node (ref "U5") (pin "152") (pinfunction "P0_14/DA0/AN005/AN105_152") (pintype "bidirectional"))
    )
    (net (code "105") (name "P015_DA1_AN006_AN106") (class "Default")
      (node (ref "U5") (pin "151") (pinfunction "P0_15/DA1/AN006/AN106_151") (pintype "bidirectional"))
    )
    (net (code "106") (name "P400_ADC") (class "Default")
      (node (ref "U5") (pin "1") (pinfunction "P4_0_1") (pintype "bidirectional"))
    )
    (net (code "107") (name "PA_00") (class "Default")
      (node (ref "U5") (pin "114") (pinfunction "PA_0_114") (pintype "bidirectional"))
    )
    (net (code "108") (name "PA_01") (class "Default")
      (node (ref "U5") (pin "113") (pinfunction "PA_1_113") (pintype "bidirectional"))
    )
    (net (code "109") (name "PA_08") (class "Default")
      (node (ref "U5") (pin "107") (pinfunction "PA_8_107") (pintype "bidirectional"))
    )
    (net (code "110") (name "PA_09") (class "Default")
      (node (ref "U5") (pin "108") (pinfunction "PA_9_108") (pintype "bidirectional"))
    )
    (net (code "111") (name "PA_10") (class "Default")
      (node (ref "U5") (pin "109") (pinfunction "PA_10_109") (pintype "bidirectional"))
    )
    (net (code "112") (name "R51") (class "Default")
      (node (ref "R23") (pin "P$1") (pinfunction "1_P$1") (pintype "passive"))
      (node (ref "U$2") (pin "12") (pinfunction "YHI_12") (pintype "bidirectional"))
    )
    (net (code "113") (name "R52") (class "Default")
      (node (ref "R24") (pin "P$1") (pinfunction "1_P$1") (pintype "passive"))
      (node (ref "U$2") (pin "9") (pinfunction "GHI_9") (pintype "bidirectional"))
    )
    (net (code "114") (name "RELAY_1") (class "Default")
      (node (ref "U5") (pin "68") (pinfunction "P2_1/MD_68") (pintype "bidirectional"))
    )
    (net (code "115") (name "RELAY_2") (class "Default")
      (node (ref "U5") (pin "54") (pinfunction "P2_2_54") (pintype "bidirectional"))
    )
    (net (code "116") (name "RELAY_3") (class "Default")
      (node (ref "U5") (pin "53") (pinfunction "P2_3_53") (pintype "bidirectional"))
    )
    (net (code "117") (name "RELAY_4") (class "Default")
      (node (ref "U5") (pin "52") (pinfunction "P2_4_52") (pintype "bidirectional"))
    )
    (net (code "118") (name "RESET") (class "Default")
      (node (ref "C29") (pin "P$1") (pinfunction "1_P$1") (pintype "passive"))
      (node (ref "J1") (pin "9") (pinfunction "9_9") (pintype "passive"))
      (node (ref "R10") (pin "P$1") (pinfunction "1_P$1") (pintype "passive"))
      (node (ref "U5") (pin "67") (pinfunction "RES#_67") (pintype "bidirectional"))
    )
    (net (code "119") (name "REXT") (class "Default")
      (node (ref "C47") (pin "P$1") (pinfunction "1_P$1") (pintype "passive"))
      (node (ref "R25") (pin "P$2") (pinfunction "2_P$2") (pintype "passive"))
      (node (ref "U3") (pin "9") (pinfunction "REXT_9") (pintype "input"))
    )
    (net (code "120") (name "RXD0") (class "Default")
      (node (ref "R31") (pin "P$2") (pinfunction "2_P$2") (pintype "passive"))
      (node (ref "U3") (pin "13") (pinfunction "RXD0_13") (pintype "bidirectional"))
    )
    (net (code "121") (name "RXD1") (class "Default")
      (node (ref "R30") (pin "P$2") (pinfunction "2_P$2") (pintype "passive"))
      (node (ref "U3") (pin "12") (pinfunction "RXD1_12") (pintype "bidirectional"))
    )
    (net (code "122") (name "RXER") (class "Default")
      (node (ref "R32") (pin "P$2") (pinfunction "2_P$2") (pintype "passive"))
      (node (ref "U3") (pin "17") (pinfunction "RXER_17") (pintype "bidirectional"))
    )
    (net (code "123") (name "RXM") (class "Default")
      (node (ref "U$2") (pin "6") (pinfunction "RD-_6") (pintype "bidirectional"))
      (node (ref "U3") (pin "3") (pinfunction "RXM_3") (pintype "bidirectional"))
    )
    (net (code "124") (name "RXP") (class "Default")
      (node (ref "U$2") (pin "3") (pinfunction "RD+_3") (pintype "bidirectional"))
      (node (ref "U3") (pin "4") (pinfunction "RXP_4") (pintype "bidirectional"))
    )
    (net (code "125") (name "TCK") (class "Default")
      (node (ref "J1") (pin "7") (pinfunction "7_7") (pintype "passive"))
      (node (ref "U5") (pin "88") (pinfunction "P3_0_88") (pintype "bidirectional"))
    )
    (net (code "126") (name "TDI") (class "Default")
      (node (ref "J1") (pin "1") (pinfunction "1_1") (pintype "passive"))
      (node (ref "U5") (pin "91") (pinfunction "P1_10_91") (pintype "bidirectional"))
    )
    (net (code "127") (name "TDO") (class "Default")
      (node (ref "J1") (pin "3") (pinfunction "3_3") (pintype "passive"))
      (node (ref "U5") (pin "90") (pinfunction "P1_9_90") (pintype "bidirectional"))
    )
    (net (code "128") (name "TMS") (class "Default")
      (node (ref "J1") (pin "5") (pinfunction "5_5") (pintype "passive"))
      (node (ref "U5") (pin "89") (pinfunction "P1_8_89") (pintype "bidirectional"))
    )
    (net (code "129") (name "TXM") (class "Default")
      (node (ref "U$2") (pin "2") (pinfunction "TD-_2") (pintype "bidirectional"))
      (node (ref "U3") (pin "5") (pinfunction "TXM_5") (pintype "bidirectional"))
    )
    (net (code "130") (name "TXP") (class "Default")
      (node (ref "U$2") (pin "1") (pinfunction "TD+_1") (pintype "bidirectional"))
      (node (ref "U3") (pin "6") (pinfunction "TXP_6") (pintype "bidirectional"))
    )
    (net (code "131") (name "USBHS_FAULT") (class "Default")
      (node (ref "R12") (pin "P$1") (pinfunction "1_P$1") (pintype "passive"))
      (node (ref "U2") (pin "3") (pinfunction "FLG_3") (pintype "input"))
      (node (ref "U5") (pin "78") (pinfunction "P3_8_78") (pintype "bidirectional"))
    )
    (net (code "132") (name "USBHS_N") (class "Default")
      (node (ref "J3") (pin "D-") (pinfunction "D-_D-") (pintype "bidirectional"))
      (node (ref "U5") (pin "31") (pinfunction "USBHS_DM_31") (pintype "bidirectional"))
    )
    (net (code "133") (name "USBHS_P") (class "Default")
      (node (ref "J3") (pin "D+") (pinfunction "D+_D+") (pintype "bidirectional"))
      (node (ref "U5") (pin "32") (pinfunction "USBHS_DP_32") (pintype "bidirectional"))
    )
    (net (code "134") (name "USBHS_VBUS") (class "Default")
      (node (ref "C11") (pin "P$1") (pinfunction "1_P$1") (pintype "passive"))
      (node (ref "C15") (pin "1") (pinfunction "1_1") (pintype "passive"))
      (node (ref "J3") (pin "VBUS") (pinfunction "VBUS_VBUS") (pintype "power_in"))
      (node (ref "U2") (pin "5") (pinfunction "OUT_5") (pintype "input"))
      (node (ref "U5") (pin "17") (pinfunction "PB_1_17") (pintype "bidirectional"))
    )
    (net (code "135") (name "USBHS_VBUSEN") (class "Default")
      (node (ref "R1") (pin "P$1") (pinfunction "1_P$1") (pintype "passive"))
      (node (ref "U2") (pin "1") (pinfunction "EN_1") (pintype "input"))
      (node (ref "U5") (pin "16") (pinfunction "PB_0_16") (pintype "bidirectional"))
    )
    (net (code "136") (name "USB_N") (class "Default")
      (node (ref "R5") (pin "P$1") (pinfunction "1_P$1") (pintype "passive"))
      (node (ref "U5") (pin "46") (pinfunction "USB_DM_46") (pintype "bidirectional"))
    )
    (net (code "137") (name "USB_P") (class "Default")
      (node (ref "R6") (pin "P$1") (pinfunction "1_P$1") (pintype "passive"))
      (node (ref "U5") (pin "47") (pinfunction "USB_DP_47") (pintype "bidirectional"))
    )
    (net (code "138") (name "USB_VBUS_B") (class "Default")
      (node (ref "R4") (pin "P$1") (pinfunction "1_P$1") (pintype "passive"))
      (node (ref "U5") (pin "44") (pinfunction "P4_7_44") (pintype "bidirectional"))
    )
    (net (code "139") (name "VCL_F(FLASH)") (class "Default")
      (node (ref "C21") (pin "P$2") (pinfunction "2_P$2") (pintype "passive"))
      (node (ref "U5") (pin "112") (pinfunction "VCL_F(FLASH)_112") (pintype "bidirectional"))
    )
    (net (code "140") (name "VDD") (class "Default")
      (node (ref "C10") (pin "P$2") (pinfunction "2_P$2") (pintype "passive"))
      (node (ref "C12") (pin "P$2") (pinfunction "2_P$2") (pintype "passive"))
      (node (ref "C13") (pin "P$2") (pinfunction "2_P$2") (pintype "passive"))
      (node (ref "C17") (pin "P$2") (pinfunction "2_P$2") (pintype "passive"))
      (node (ref "C22") (pin "P$2") (pinfunction "2_P$2") (pintype "passive"))
      (node (ref "C23") (pin "P$1") (pinfunction "1_P$1") (pintype "passive"))
      (node (ref "C25") (pin "P$2") (pinfunction "2_P$2") (pintype "passive"))
      (node (ref "C26") (pin "P$1") (pinfunction "1_P$1") (pintype "passive"))
      (node (ref "C27") (pin "P$1") (pinfunction "1_P$1") (pintype "passive"))
      (node (ref "C30") (pin "P$1") (pinfunction "1_P$1") (pintype "passive"))
      (node (ref "C31") (pin "P$2") (pinfunction "2_P$2") (pintype "passive"))
      (node (ref "C33") (pin "P$1") (pinfunction "1_P$1") (pintype "passive"))
      (node (ref "C34") (pin "P$1") (pinfunction "1_P$1") (pintype "passive"))
      (node (ref "C35") (pin "P$1") (pinfunction "1_P$1") (pintype "passive"))
      (node (ref "C48") (pin "1") (pinfunction "1_1") (pintype "passive"))
      (node (ref "C49") (pin "P$1") (pinfunction "1_P$1") (pintype "passive"))
      (node (ref "C6") (pin "P$2") (pinfunction "2_P$2") (pintype "passive"))
      (node (ref "FB2/2") (pin "1") (pinfunction "P$1_1") (pintype "bidirectional"))
      (node (ref "J1") (pin "2") (pinfunction "2_2") (pintype "passive"))
      (node (ref "J1") (pin "4") (pinfunction "4_4") (pintype "passive"))
      (node (ref "L3") (pin "2") (pinfunction "P$2_2") (pintype "bidirectional"))
      (node (ref "R10") (pin "P$2") (pinfunction "2_P$2") (pintype "passive"))
      (node (ref "R13") (pin "P$2") (pinfunction "2_P$2") (pintype "passive"))
      (node (ref "R23") (pin "P$2") (pinfunction "2_P$2") (pintype "passive"))
      (node (ref "R24") (pin "P$2") (pinfunction "2_P$2") (pintype "passive"))
      (node (ref "R26") (pin "P$2") (pinfunction "2_P$2") (pintype "passive"))
      (node (ref "R27") (pin "P$2") (pinfunction "2_P$2") (pintype "passive"))
      (node (ref "R28") (pin "P$2") (pinfunction "2_P$2") (pintype "passive"))
      (node (ref "R29") (pin "P$2") (pinfunction "2_P$2") (pintype "passive"))
      (node (ref "U3") (pin "14") (pinfunction "VDDIO_14") (pintype "power_in"))
      (node (ref "U5") (pin "110") (pinfunction "VCC(IO)5_110") (pintype "bidirectional"))
      (node (ref "U5") (pin "123") (pinfunction "VCC(IO)6_123") (pintype "bidirectional"))
      (node (ref "U5") (pin "138") (pinfunction "VCC(IO)7_138") (pintype "bidirectional"))
      (node (ref "U5") (pin "149") (pinfunction "VCC(IO)8_149") (pintype "bidirectional"))
      (node (ref "U5") (pin "155") (pinfunction "AVCC0_155") (pintype "bidirectional"))
      (node (ref "U5") (pin "171") (pinfunction "VCC(IO)9_171") (pintype "bidirectional"))
      (node (ref "U5") (pin "25") (pinfunction "VCC1_25") (pintype "bidirectional"))
      (node (ref "U5") (pin "26") (pinfunction "AVCC_SUBHS_26") (pintype "bidirectional"))
      (node (ref "U5") (pin "34") (pinfunction "VCC_USBHS_34") (pintype "bidirectional"))
      (node (ref "U5") (pin "48") (pinfunction "VCC_USB_48") (pintype "bidirectional"))
      (node (ref "U5") (pin "61") (pinfunction "VCC(IO)2_61") (pintype "bidirectional"))
      (node (ref "U5") (pin "84") (pinfunction "VCC(IO)3_84") (pintype "bidirectional"))
      (node (ref "U5") (pin "97") (pinfunction "VCC(IO)4_97") (pintype "bidirectional"))
    )
    (net (code "141") (name "VDD5") (class "Default")
      (node (ref "C5") (pin "P$1") (pinfunction "1_P$1") (pintype "passive"))
      (node (ref "C8") (pin "P$1") (pinfunction "1_P$1") (pintype "passive"))
      (node (ref "J6") (pin "5") (pinfunction "5_5") (pintype "passive"))
      (node (ref "J6") (pin "6") (pinfunction "6_6") (pintype "passive"))
      (node (ref "R1") (pin "P$2") (pinfunction "2_P$2") (pintype "passive"))
      (node (ref "R12") (pin "P$2") (pinfunction "2_P$2") (pintype "passive"))
      (node (ref "U2") (pin "4") (pinfunction "VIN_4") (pintype "input"))
    )
    (net (code "142") (name "VDD12") (class "Default")
      (node (ref "J6") (pin "7") (pinfunction "7_7") (pintype "passive"))
      (node (ref "J6") (pin "8") (pinfunction "8_8") (pintype "passive"))
    )
    (net (code "143") (name "VDDIN") (class "Default")
      (node (ref "J6") (pin "3") (pinfunction "3_3") (pintype "passive"))
      (node (ref "J6") (pin "4") (pinfunction "4_4") (pintype "passive"))
      (node (ref "L3") (pin "1") (pinfunction "P$1_1") (pintype "bidirectional"))
    )
    (net (code "144") (name "VDD_1.2") (class "Default")
      (node (ref "C45") (pin "P$1") (pinfunction "1_P$1") (pintype "passive"))
      (node (ref "C46") (pin "P$1") (pinfunction "1_P$1") (pintype "passive"))
      (node (ref "U3") (pin "1") (pinfunction "VDD_1.2_1") (pintype "power_in"))
    )
    (net (code "145") (name "XCIN") (class "Default")
      (node (ref "C19") (pin "P$1") (pinfunction "1_P$1") (pintype "passive"))
      (node (ref "U5") (pin "20") (pinfunction "XCIN_20") (pintype "bidirectional"))
      (node (ref "X2") (pin "P$1") (pinfunction "P$1_P$1") (pintype "bidirectional"))
    )
    (net (code "146") (name "XCOUT") (class "Default")
      (node (ref "C24") (pin "P$1") (pinfunction "1_P$1") (pintype "passive"))
      (node (ref "U5") (pin "21") (pinfunction "XCOUT_21") (pintype "bidirectional"))
      (node (ref "X2") (pin "P$2") (pinfunction "P$2_P$2") (pintype "bidirectional"))
    )
    (net (code "147") (name "XII") (class "Default")
      (node (ref "C42") (pin "P$1") (pinfunction "1_P$1") (pintype "passive"))
      (node (ref "U$3") (pin "1") (pinfunction "1_1") (pintype "bidirectional"))
      (node (ref "U3") (pin "8") (pinfunction "XI_8") (pintype "input"))
    )
    (net (code "148") (name "XOO") (class "Default")
      (node (ref "C41") (pin "P$1") (pinfunction "1_P$1") (pintype "passive"))
      (node (ref "U$3") (pin "3") (pinfunction "3_3") (pintype "bidirectional"))
      (node (ref "U3") (pin "7") (pinfunction "XO_7") (pintype "output"))
    )
    (net (code "149") (name "XTAL1") (class "Default")
      (node (ref "C7") (pin "P$1") (pinfunction "1_P$1") (pintype "passive"))
      (node (ref "U5") (pin "23") (pinfunction "P2_13/XTAL_23") (pintype "bidirectional"))
      (node (ref "X1") (pin "1") (pinfunction "1_1") (pintype "bidirectional"))
    )
    (net (code "150") (name "XTAL2") (class "Default")
      (node (ref "C14") (pin "P$1") (pinfunction "1_P$1") (pintype "passive"))
      (node (ref "U5") (pin "24") (pinfunction "P2_12/EXTAL_24") (pintype "bidirectional"))
      (node (ref "X1") (pin "3") (pinfunction "3_3") (pintype "bidirectional"))
    )
    (net (code "151") (name "X_DIR") (class "Default")
      (node (ref "U5") (pin "118") (pinfunction "P6_4_118") (pintype "bidirectional"))
    )
    (net (code "152") (name "X_LS") (class "Default")
      (node (ref "U5") (pin "164") (pinfunction "P0_5/AN101_164") (pintype "bidirectional"))
    )
    (net (code "153") (name "X_STEP") (class "Default")
      (node (ref "U5") (pin "86") (pinfunction "P3_2_86") (pintype "bidirectional"))
    )
    (net (code "154") (name "Y_DIR") (class "Default")
      (node (ref "U5") (pin "115") (pinfunction "P6_7_115") (pintype "bidirectional"))
    )
    (net (code "155") (name "Y_LS") (class "Default")
      (node (ref "U5") (pin "175") (pinfunction "P5_12_175") (pintype "bidirectional"))
    )
    (net (code "156") (name "Y_STEP") (class "Default")
      (node (ref "U5") (pin "82") (pinfunction "P3_4_82") (pintype "bidirectional"))
    )
    (net (code "157") (name "Z_DIR") (class "Default")
      (node (ref "U5") (pin "121") (pinfunction "P6_1_121") (pintype "bidirectional"))
    )
    (net (code "158") (name "Z_LS") (class "Default")
      (node (ref "U5") (pin "169") (pinfunction "P0_0/AN0\\00_169") (pintype "bidirectional"))
    )
    (net (code "159") (name "Z_STEP") (class "Default")
      (node (ref "U5") (pin "92") (pinfunction "P1_11_92") (pintype "bidirectional"))
    )
    (net (code "160") (name "unconnected-(U$2-GNDE0-Pad13)") (class "Default")
      (node (ref "U$2") (pin "13") (pinfunction "GNDE0_13") (pintype "bidirectional"))
    )
    (net (code "161") (name "unconnected-(U$2-GNDE1-Pad14)") (class "Default")
      (node (ref "U$2") (pin "14") (pinfunction "GNDE1_14") (pintype "bidirectional"))
    )
    (net (code "162") (name "unconnected-(U5-P4_1-Pad2)") (class "Default")
      (node (ref "U5") (pin "2") (pinfunction "P4_1_2") (pintype "bidirectional"))
    )
    (net (code "163") (name "unconnected-(U5-P4_2-Pad3)") (class "Default")
      (node (ref "U5") (pin "3") (pinfunction "P4_2_3") (pintype "bidirectional"))
    )
    (net (code "164") (name "unconnected-(U5-P4_8-Pad43)") (class "Default")
      (node (ref "U5") (pin "43") (pinfunction "P4_8_43") (pintype "bidirectional"))
    )
    (net (code "165") (name "unconnected-(U5-P4_10-Pad41)") (class "Default")
      (node (ref "U5") (pin "41") (pinfunction "P4_10_41") (pintype "bidirectional"))
    )
    (net (code "166") (name "unconnected-(U5-P4_11-Pad40)") (class "Default")
      (node (ref "U5") (pin "40") (pinfunction "P4_11_40") (pintype "bidirectional"))
    )
    (net (code "167") (name "unconnected-(U5-P4_12-Pad39)") (class "Default")
      (node (ref "U5") (pin "39") (pinfunction "P4_12_39") (pintype "bidirectional"))
    )
    (net (code "168") (name "unconnected-(U5-P4_13-Pad38)") (class "Default")
      (node (ref "U5") (pin "38") (pinfunction "P4_13_38") (pintype "bidirectional"))
    )
    (net (code "169") (name "unconnected-(U5-P4_14-Pad37)") (class "Default")
      (node (ref "U5") (pin "37") (pinfunction "P4_14_37") (pintype "bidirectional"))
    )
    (net (code "170") (name "unconnected-(U5-P4_15-Pad36)") (class "Default")
      (node (ref "U5") (pin "36") (pinfunction "P4_15_36") (pintype "bidirectional"))
    )
    (net (code "171") (name "unconnected-(U5-P7_6-Pad14)") (class "Default")
      (node (ref "U5") (pin "14") (pinfunction "P7_6_14") (pintype "bidirectional"))
    )
    (net (code "172") (name "unconnected-(U5-P7_7-Pad15)") (class "Default")
      (node (ref "U5") (pin "15") (pinfunction "P7_7_15") (pintype "bidirectional"))
    )
    (net (code "173") (name "unconnected-(U5-VBAT-Pad18)") (class "Default")
      (node (ref "U5") (pin "18") (pinfunction "VBAT_18") (pintype "bidirectional"))
    )
    (net (code "174") (name "unconnected-(U5-VREFH-Pad154)") (class "Default")
      (node (ref "U5") (pin "154") (pinfunction "VREFH_154") (pintype "bidirectional"))
    )
    (net (code "175") (name "unconnected-(U5-VREFH0-Pad158)") (class "Default")
      (node (ref "U5") (pin "158") (pinfunction "VREFH0_158") (pintype "bidirectional"))
    )
    (net (code "176") (name "unconnected-(U5-VREFL-Pad153)") (class "Default")
      (node (ref "U5") (pin "153") (pinfunction "VREFL_153") (pintype "bidirectional"))
    )
    (net (code "177") (name "unconnected-(U5-VREFL0-Pad157)") (class "Default")
      (node (ref "U5") (pin "157") (pinfunction "VREFL0_157") (pintype "bidirectional"))
    )
  )
)
